# SCH_VCNL4010_2023-08-02.net
KiCad netlist of a schematic drawn in EasyEDA
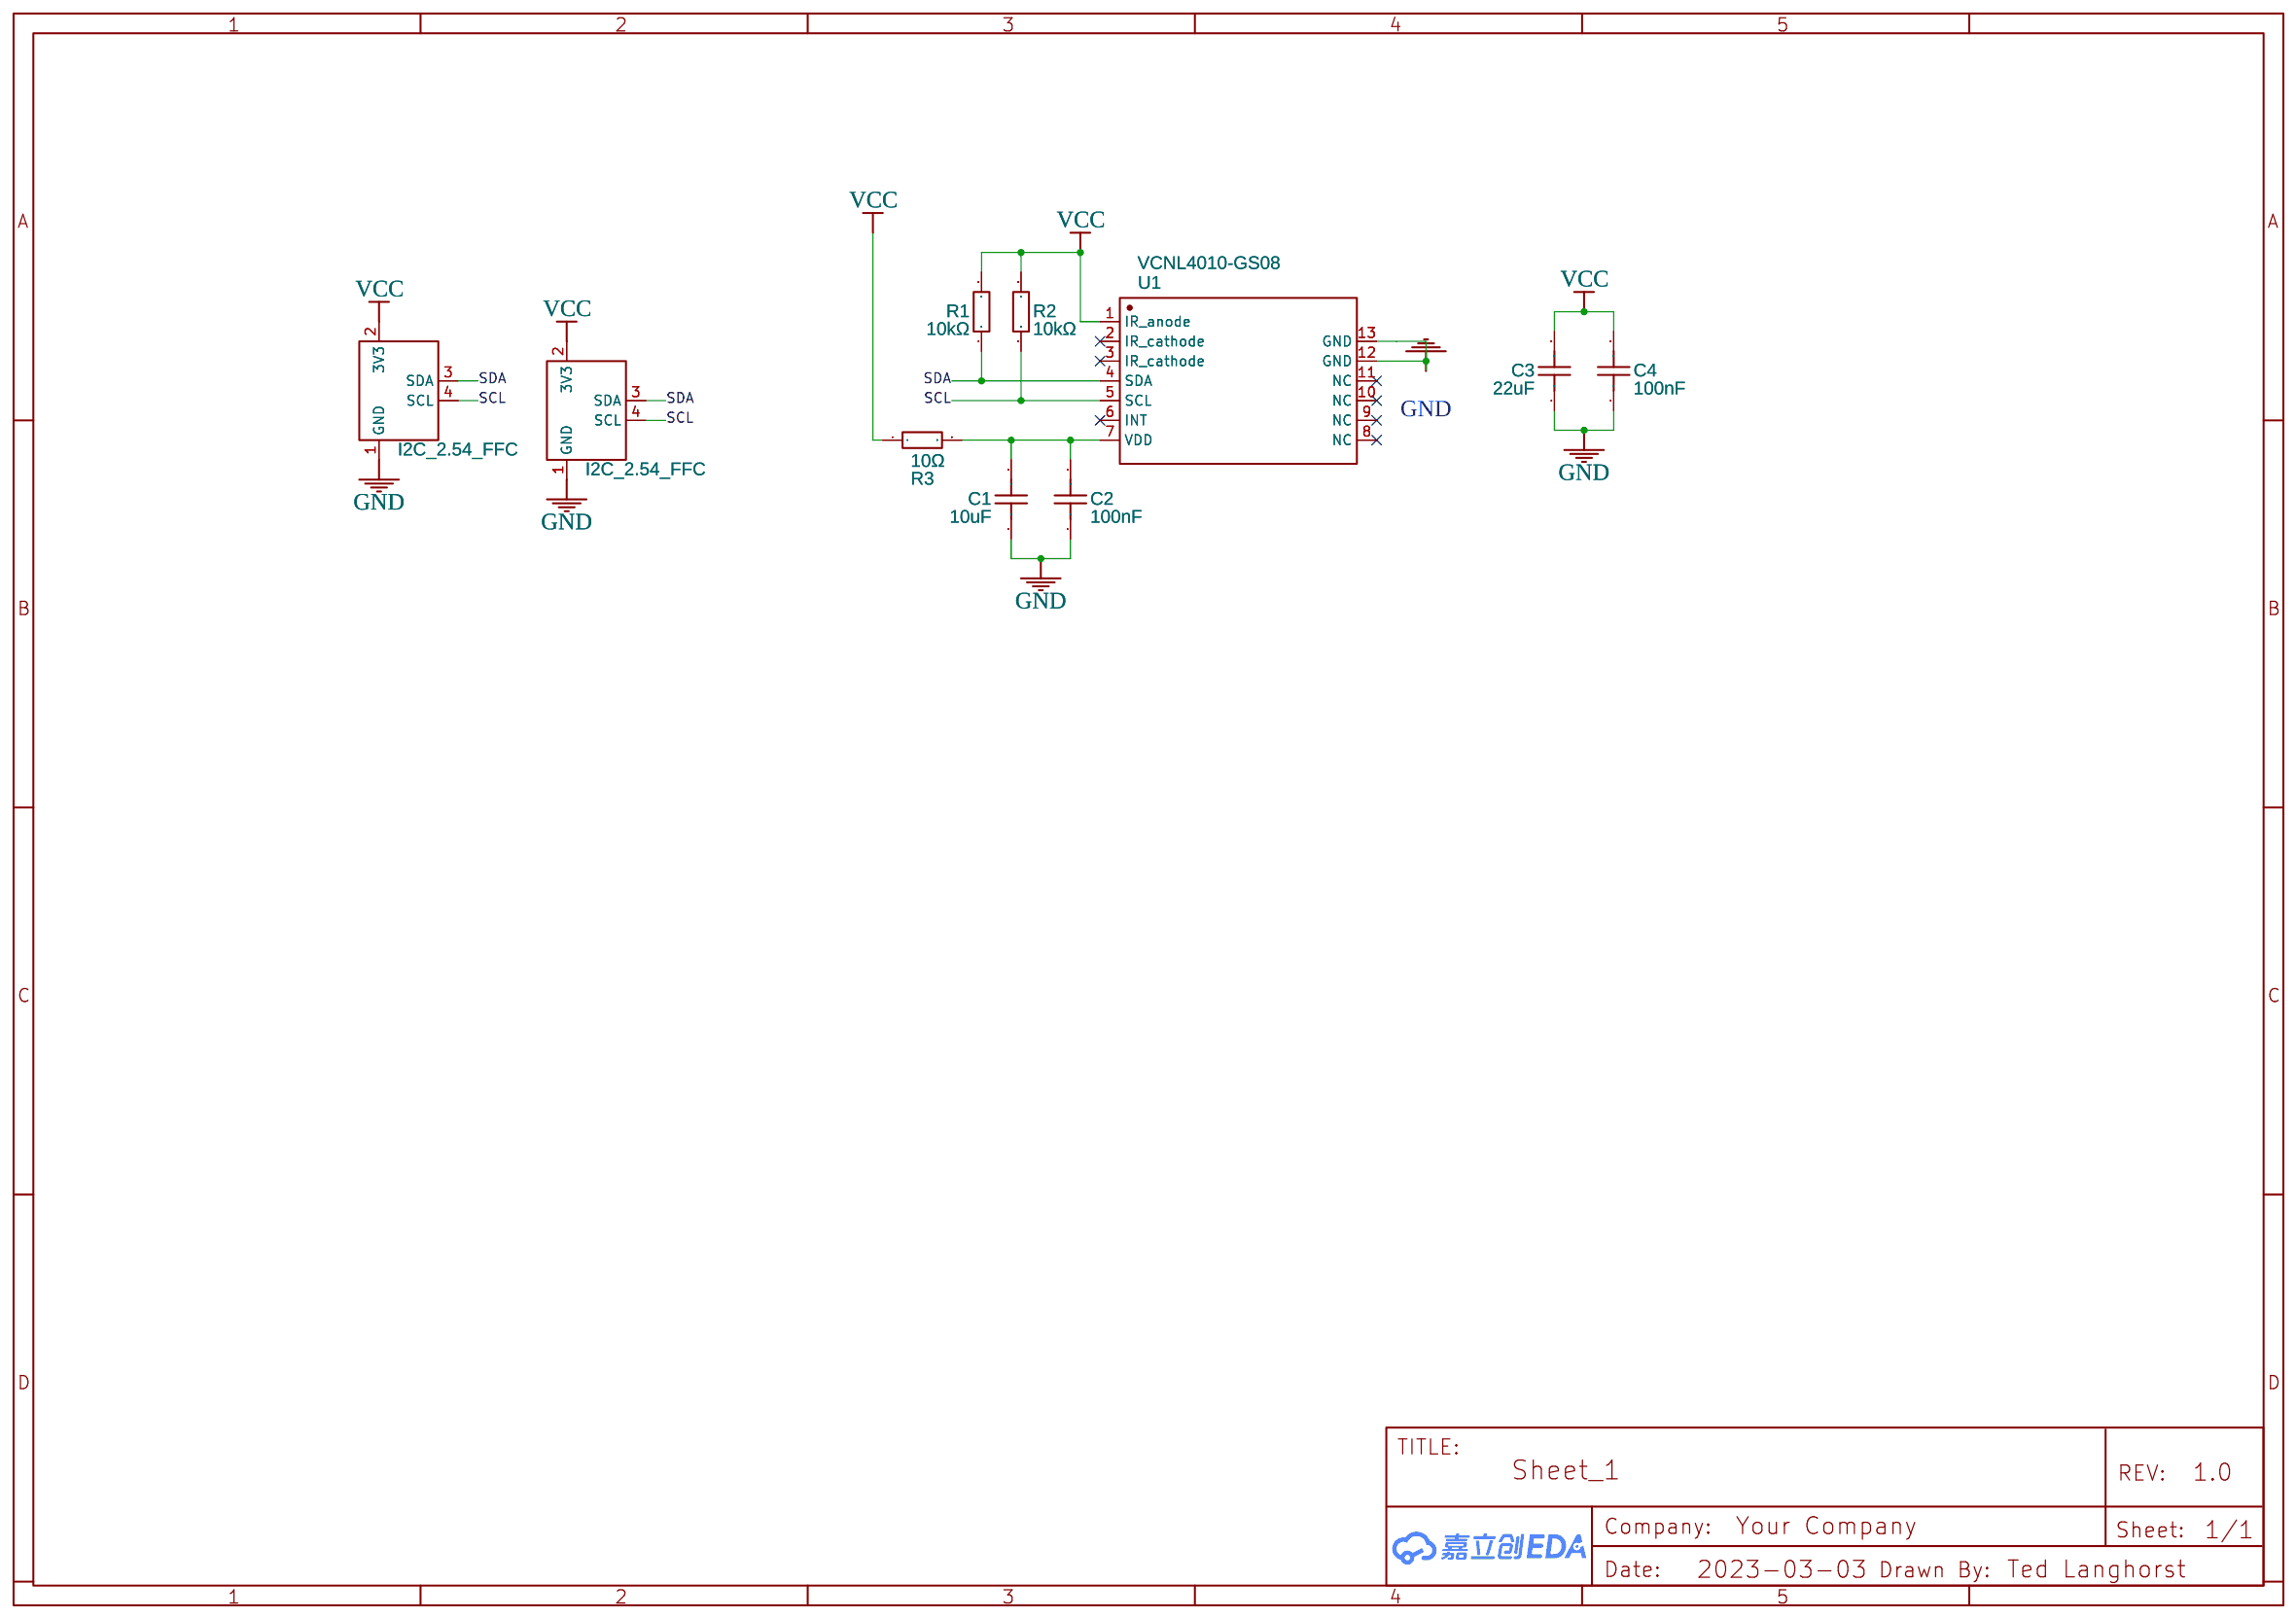
[diagram p0: schematic sheet]

(export (version "E")
  (design (tool "Eeschema 10.0.6"))
  (components
    (comp (ref "C1")
      (value "10uF")
      (fields
        (field (name "Manufacturer Part") "CL10A106MA8NRNC")
        (field (name "Manufacturer") "SAMSUNG(三星)")
      )
      (libsource (lib "") (part "CL10A106MA8NRNC"))
    )
    (comp (ref "C2")
      (value "100nF")
      (fields
        (field (name "Manufacturer Part") "CC0603KRX7R9BB104")
        (field (name "Manufacturer") "YAGEO(国巨)")
      )
      (libsource (lib "") (part "CC0603KRX7R9BB104"))
    )
    (comp (ref "C3")
      (value "22uF")
      (fields
        (field (name "Manufacturer Part") "CL10A226MQ8NRNC")
        (field (name "Manufacturer") "SAMSUNG(三星)")
      )
      (libsource (lib "") (part "CL10A226MQ8NRNC"))
    )
    (comp (ref "C4")
      (value "100nF")
      (fields
        (field (name "Manufacturer Part") "CC0603KRX7R9BB104")
        (field (name "Manufacturer") "YAGEO(国巨)")
      )
      (libsource (lib "") (part "CC0603KRX7R9BB104"))
    )
    (comp (ref "R1")
      (value "10kΩ")
      (fields
        (field (name "Manufacturer Part") "0603WAF1002T5E")
        (field (name "Manufacturer") "UNI-ROYAL(厚声)")
      )
      (libsource (lib "") (part "0603WAF1002T5E"))
    )
    (comp (ref "R2")
      (value "10kΩ")
      (fields
        (field (name "Manufacturer Part") "0603WAF1002T5E")
        (field (name "Manufacturer") "UNI-ROYAL(厚声)")
      )
      (libsource (lib "") (part "0603WAF1002T5E"))
    )
    (comp (ref "R3")
      (value "10Ω")
      (fields
        (field (name "Manufacturer Part") "0603WAF100JT5E")
        (field (name "Manufacturer") "UNI-ROYAL(厚声)")
      )
      (libsource (lib "") (part "0603WAF100JT5E"))
    )
    (comp (ref "U1")
      (value "VCNL4010-GS08")
      (fields (field (name "Manufacturer") "VISHAY(威世)"))
      (libsource (lib "") (part "VCNL4010-GS08"))
    )
    (comp (ref "U2")
      (value "I2C_2.54_FFC")
      (fields
        (field (name "Manufacturer Part") "5-1474644-0")
        (field (name "Manufacturer") "TE Connectivity AMP Connectors")
      )
      (libsource (lib "") (part "I2C_2.54_FFC"))
    )
    (comp (ref "U3")
      (value "I2C_2.54_FFC")
      (fields
        (field (name "Manufacturer Part") "5-1474644-0")
        (field (name "Manufacturer") "TE Connectivity AMP Connectors")
      )
      (libsource (lib "") (part "I2C_2.54_FFC"))
    )
  )
  (nets
    (net (code "1") (name "/SCL") (class "Default")
      (node (ref "R2") (pin "1") (pinfunction "1_1") (pintype "input"))
      (node (ref "U1") (pin "5") (pinfunction "SCL_5") (pintype "unspecified"))
      (node (ref "U2") (pin "4") (pinfunction "SCL_4") (pintype "unspecified"))
      (node (ref "U3") (pin "4") (pinfunction "SCL_4") (pintype "unspecified"))
    )
    (net (code "2") (name "/SDA") (class "Default")
      (node (ref "R1") (pin "1") (pinfunction "1_1") (pintype "input"))
      (node (ref "U1") (pin "4") (pinfunction "SDA_4") (pintype "unspecified"))
      (node (ref "U2") (pin "3") (pinfunction "SDA_3") (pintype "unspecified"))
      (node (ref "U3") (pin "3") (pinfunction "SDA_3") (pintype "unspecified"))
    )
    (net (code "3") (name "GND") (class "Default")
      (node (ref "C1") (pin "1") (pinfunction "1_1") (pintype "unspecified"))
      (node (ref "C2") (pin "1") (pinfunction "1_1") (pintype "unspecified"))
      (node (ref "C3") (pin "1") (pinfunction "1_1") (pintype "unspecified"))
      (node (ref "C4") (pin "1") (pinfunction "1_1") (pintype "unspecified"))
      (node (ref "U1") (pin "12") (pinfunction "GND_12") (pintype "unspecified"))
      (node (ref "U1") (pin "13") (pinfunction "GND_13") (pintype "unspecified"))
      (node (ref "U2") (pin "1") (pinfunction "GND_1") (pintype "unspecified"))
      (node (ref "U3") (pin "1") (pinfunction "GND_1") (pintype "unspecified"))
    )
    (net (code "4") (name "Net-(U1-VDD)") (class "Default")
      (node (ref "C1") (pin "2") (pinfunction "2_2") (pintype "unspecified"))
      (node (ref "C2") (pin "2") (pinfunction "2_2") (pintype "unspecified"))
      (node (ref "R3") (pin "2") (pinfunction "2_2") (pintype "input"))
      (node (ref "U1") (pin "7") (pinfunction "VDD_7") (pintype "unspecified"))
    )
    (net (code "5") (name "VCC") (class "Default")
      (node (ref "C3") (pin "2") (pinfunction "2_2") (pintype "unspecified"))
      (node (ref "C4") (pin "2") (pinfunction "2_2") (pintype "unspecified"))
      (node (ref "R1") (pin "2") (pinfunction "2_2") (pintype "input"))
      (node (ref "R2") (pin "2") (pinfunction "2_2") (pintype "input"))
      (node (ref "R3") (pin "1") (pinfunction "1_1") (pintype "input"))
      (node (ref "U1") (pin "1") (pinfunction "IR_anode_1") (pintype "unspecified"))
      (node (ref "U2") (pin "2") (pinfunction "3V3_2") (pintype "unspecified"))
      (node (ref "U3") (pin "2") (pinfunction "3V3_2") (pintype "unspecified"))
    )
    (net (code "6") (name "unconnected-(U1-INT-Pad6)") (class "Default")
      (node (ref "U1") (pin "6") (pinfunction "INT_6") (pintype "unspecified+no_connect"))
    )
    (net (code "7") (name "unconnected-(U1-IR_cathode-Pad2)") (class "Default")
      (node (ref "U1") (pin "2") (pinfunction "IR_cathode_2") (pintype "unspecified+no_connect"))
    )
    (net (code "8") (name "unconnected-(U1-IR_cathode-Pad3)") (class "Default")
      (node (ref "U1") (pin "3") (pinfunction "IR_cathode_3") (pintype "unspecified+no_connect"))
    )
    (net (code "9") (name "unconnected-(U1-NC-Pad8)") (class "Default")
      (node (ref "U1") (pin "8") (pinfunction "NC_8") (pintype "unspecified+no_connect"))
    )
    (net (code "10") (name "unconnected-(U1-NC-Pad9)") (class "Default")
      (node (ref "U1") (pin "9") (pinfunction "NC_9") (pintype "unspecified+no_connect"))
    )
    (net (code "11") (name "unconnected-(U1-NC-Pad10)") (class "Default")
      (node (ref "U1") (pin "10") (pinfunction "NC_10") (pintype "unspecified+no_connect"))
    )
    (net (code "12") (name "unconnected-(U1-NC-Pad11)") (class "Default")
      (node (ref "U1") (pin "11") (pinfunction "NC_11") (pintype "unspecified+no_connect"))
    )
  )
)
